# 3V3_LDO.net
KiCad netlist of a schematic drawn in Altium Designer
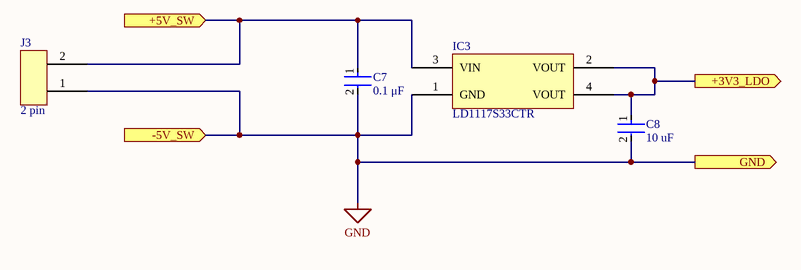
[diagram p0: 3V3 LDO.SchDoc]

(export (version "E")
  (design (tool "Eeschema 10.0.6"))
  (components
    (comp (ref "C7")
      (value "0.1 μF")
      (footprint "FP-C0805C-DN-MFG")
      (description "C0805 0.10 μF X7R 30ppm/°C 20.00% 50 V C0805C104M5RAC")
      (fields
        (field (name "MANUFACTURER PART NUMBER") "C0805C104M5RAC")
        (field (name "MANUFACTURER") "KEMET")
      )
      (libsource (lib "Altium Content Vault") (part "b4654b650e69147ec39a6b967a45e02"))
    )
    (comp (ref "C8")
      (value "10 uF")
      (footprint "FP-C0805C-DG-MFG")
      (description "CAP CER 10UF 10V X5R 0805\r\nC0805C106K8PACTU")
      (fields (field (name "TOLERANCE") "10%") (field (name "MANUFACTURER PART NUMBER") "C0805C106K8PACTU"))
      (libsource (lib "Altium Content Vault") (part "11868f565c42a9108669ba33697ecf6"))
    )
    (comp (ref "IC3")
      (value "LD1117S33CTR")
      (footprint "LD1117")
      (description "IC REG LINEAR 3.3V 800MA SOT223")
      (libsource (lib "Callisto Control Board") (part "LD1117S33CTR"))
    )
    (comp (ref "J3")
      (value "2 pin")
      (footprint "TB003-500-P02BE")
      (libsource (lib "Callisto Control Board") (part "TB003-500-P02BE"))
    )
  )
  (nets
    (net (code "1") (name "/+3V3_LDO") (class "Default")
      (node (ref "C8") (pin "1") (pinfunction "1_1") (pintype "passive"))
      (node (ref "IC3") (pin "2") (pinfunction "VOUT_2") (pintype "passive"))
      (node (ref "IC3") (pin "4") (pinfunction "VOUT_4") (pintype "passive"))
    )
    (net (code "2") (name "/+5V_SW") (class "Default")
      (node (ref "C7") (pin "1") (pinfunction "1_1") (pintype "passive"))
      (node (ref "IC3") (pin "3") (pinfunction "VIN_3") (pintype "passive"))
      (node (ref "J3") (pin "2") (pintype "passive"))
    )
    (net (code "3") (name "GND") (class "Default")
      (node (ref "C7") (pin "2") (pinfunction "2_2") (pintype "passive"))
      (node (ref "C8") (pin "2") (pinfunction "2_2") (pintype "passive"))
      (node (ref "IC3") (pin "1") (pinfunction "GND_1") (pintype "passive"))
      (node (ref "J3") (pin "1") (pintype "passive"))
    )
  )
)
